# j310_lna.net
KiCad netlist of a schematic drawn in EAGLE
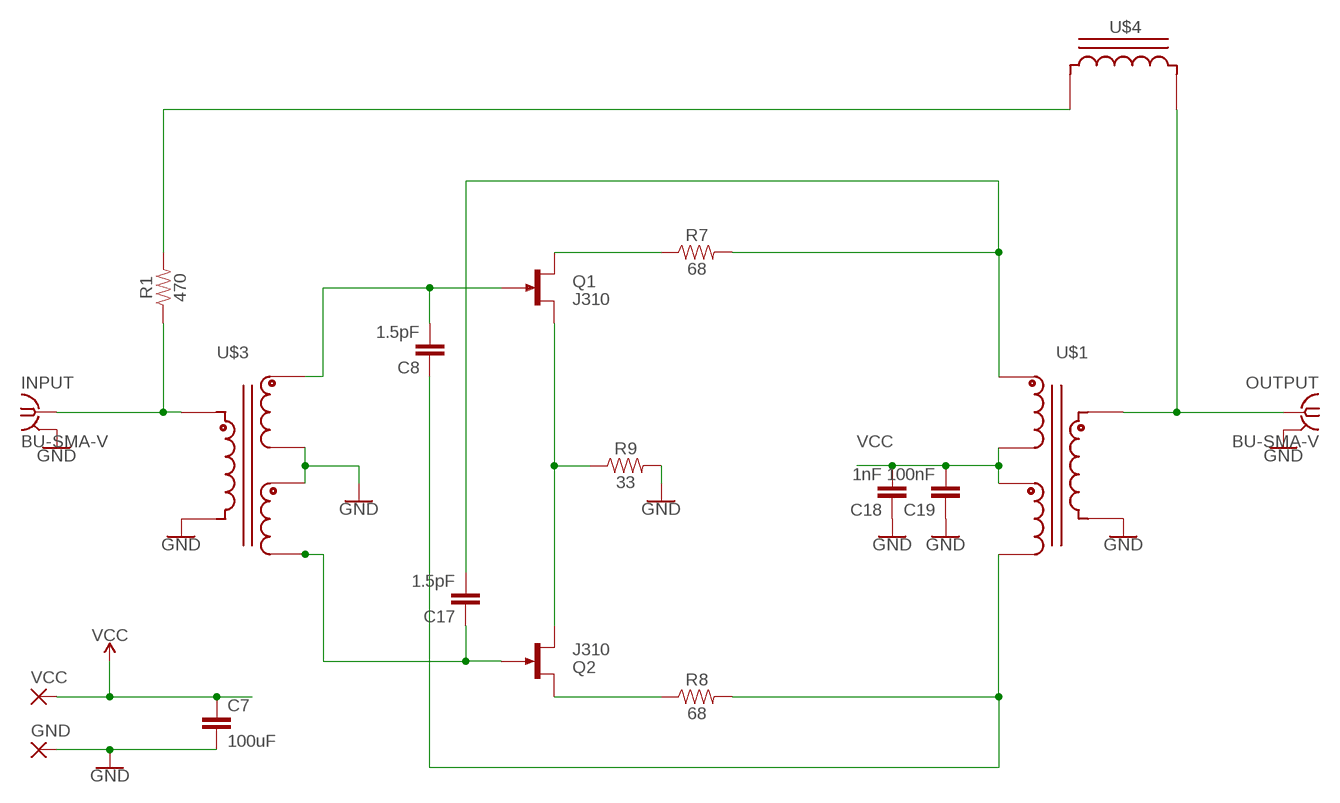
[diagram p0: schematic, sheet 1]

(export (version "E")
  (design (tool "Eeschema 10.0.6"))
  (components
    (comp (ref "C7")
      (value "100uF")
      (footprint "eagle-import:C5B3.5")
      (libsource (lib "eagle-import") (part "C5/3.5"))
    )
    (comp (ref "C8")
      (value "1.5pF")
      (footprint "eagle-import:C5B3.5")
      (libsource (lib "eagle-import") (part "C5/3.5"))
    )
    (comp (ref "C17")
      (value "1.5pF")
      (footprint "eagle-import:C5B3.5")
      (libsource (lib "eagle-import") (part "C5/3.5"))
    )
    (comp (ref "C18")
      (value "1nF")
      (footprint "eagle-import:C5B3.5")
      (libsource (lib "eagle-import") (part "C5/3.5"))
    )
    (comp (ref "C19")
      (value "100nF")
      (footprint "eagle-import:C5B3.5")
      (libsource (lib "eagle-import") (part "C5/3.5"))
    )
    (comp (ref "GND")
      (value "3,17/1,1")
      (footprint "eagle-import:3,17_1,1")
      (libsource (lib "eagle-import") (part "3,17/1,1"))
    )
    (comp (ref "INPUT")
      (value "BU-SMA-V")
      (footprint "eagle-import:BU-SMA-V")
      (libsource (lib "eagle-import") (part "BU-SMA-V"))
    )
    (comp (ref "OUTPUT")
      (value "BU-SMA-V")
      (footprint "eagle-import:BU-SMA-V")
      (libsource (lib "eagle-import") (part "BU-SMA-V"))
    )
    (comp (ref "Q1")
      (value "J310")
      (footprint "eagle-import:TO92R")
      (libsource (lib "eagle-import") (part "J310"))
    )
    (comp (ref "Q2")
      (value "J310")
      (footprint "eagle-import:TO92R")
      (libsource (lib "eagle-import") (part "J310"))
    )
    (comp (ref "R1")
      (value "470")
      (footprint "eagle-import:AXIAL-0.3")
      (libsource (lib "eagle-import") (part "1KOHM-HORIZ-1/4W-1%"))
    )
    (comp (ref "R7")
      (value "68")
      (footprint "eagle-import:AXIAL-0.3")
      (libsource (lib "eagle-import") (part "1KOHM-HORIZ-1/4W-1%"))
    )
    (comp (ref "R8")
      (value "68")
      (footprint "eagle-import:AXIAL-0.3")
      (libsource (lib "eagle-import") (part "1KOHM-HORIZ-1/4W-1%"))
    )
    (comp (ref "R9")
      (value "33")
      (footprint "eagle-import:AXIAL-0.3")
      (libsource (lib "eagle-import") (part "1KOHM-HORIZ-1/4W-1%"))
    )
    (comp (ref "U$1")
      (value "T50_SPLITTER")
      (footprint "eagle-import:T50_SPLITTER")
      (libsource (lib "eagle-import") (part "T50_SPLITTER"))
    )
    (comp (ref "U$3")
      (value "T50_SPLITTER")
      (footprint "eagle-import:T50_SPLITTER")
      (libsource (lib "eagle-import") (part "T50_SPLITTER"))
    )
    (comp (ref "U$4")
      (value "T37_INDUCTOR")
      (footprint "eagle-import:T37_INDUCTOR")
      (libsource (lib "eagle-import") (part "T37_INDUCTOR"))
    )
    (comp (ref "VCC")
      (value "3,17/1,1")
      (footprint "eagle-import:3,17_1,1")
      (libsource (lib "eagle-import") (part "3,17/1,1"))
    )
  )
  (nets
    (net (code "1") (name "GND") (class "Default")
      (node (ref "C18") (pin "1") (pinfunction "1_1") (pintype "passive"))
      (node (ref "C19") (pin "1") (pinfunction "1_1") (pintype "passive"))
      (node (ref "C7") (pin "2") (pinfunction "2_2") (pintype "passive"))
      (node (ref "GND") (pin "1") (pinfunction "P_1") (pintype "passive"))
      (node (ref "INPUT") (pin "2") (pinfunction "2_2") (pintype "passive"))
      (node (ref "INPUT") (pin "3") (pinfunction "2_3") (pintype "passive"))
      (node (ref "INPUT") (pin "4") (pinfunction "2_4") (pintype "passive"))
      (node (ref "INPUT") (pin "5") (pinfunction "2_5") (pintype "passive"))
      (node (ref "OUTPUT") (pin "2") (pinfunction "2_2") (pintype "passive"))
      (node (ref "OUTPUT") (pin "3") (pinfunction "2_3") (pintype "passive"))
      (node (ref "OUTPUT") (pin "4") (pinfunction "2_4") (pintype "passive"))
      (node (ref "OUTPUT") (pin "5") (pinfunction "2_5") (pintype "passive"))
      (node (ref "R9") (pin "P$2") (pinfunction "2_P$2") (pintype "passive"))
      (node (ref "U$1") (pin "C1A") (pinfunction "C1A_C1A") (pintype "bidirectional"))
      (node (ref "U$3") (pin "C1A") (pinfunction "C1A_C1A") (pintype "bidirectional"))
      (node (ref "U$3") (pin "C2A") (pinfunction "C3B_C2A") (pintype "bidirectional"))
      (node (ref "U$3") (pin "C3A") (pinfunction "C2A_C3A") (pintype "bidirectional"))
    )
    (net (code "2") (name "Net-(OUTPUT-Pad1)") (class "Default")
      (node (ref "OUTPUT") (pin "1") (pinfunction "1_1") (pintype "passive"))
      (node (ref "U$1") (pin "C1B") (pinfunction "C1B_C1B") (pintype "bidirectional"))
      (node (ref "U$4") (pin "CA") (pinfunction "CA_CA") (pintype "bidirectional"))
    )
    (net (code "3") (name "Net-(R1-1)") (class "Default")
      (node (ref "INPUT") (pin "1") (pinfunction "1_1") (pintype "passive"))
      (node (ref "R1") (pin "P$1") (pinfunction "1_P$1") (pintype "passive"))
      (node (ref "U$3") (pin "C1B") (pinfunction "C1B_C1B") (pintype "bidirectional"))
    )
    (net (code "4") (name "Net-(R1-2)") (class "Default")
      (node (ref "R1") (pin "P$2") (pinfunction "2_P$2") (pintype "passive"))
      (node (ref "U$4") (pin "CB") (pinfunction "CB_CB") (pintype "bidirectional"))
    )
    (net (code "5") (name "Net-(R7-1)") (class "Default")
      (node (ref "Q1") (pin "D") (pinfunction "D_D") (pintype "passive"))
      (node (ref "R7") (pin "P$1") (pinfunction "1_P$1") (pintype "passive"))
    )
    (net (code "6") (name "Net-(R7-2)") (class "Default")
      (node (ref "C17") (pin "2") (pinfunction "2_2") (pintype "passive"))
      (node (ref "R7") (pin "P$2") (pinfunction "2_P$2") (pintype "passive"))
      (node (ref "U$1") (pin "C3B") (pinfunction "C2B_C3B") (pintype "bidirectional"))
    )
    (net (code "7") (name "Net-(R8-1)") (class "Default")
      (node (ref "Q2") (pin "D") (pinfunction "D_D") (pintype "passive"))
      (node (ref "R8") (pin "P$1") (pinfunction "1_P$1") (pintype "passive"))
    )
    (net (code "8") (name "Net-(R8-2)") (class "Default")
      (node (ref "C8") (pin "1") (pinfunction "1_1") (pintype "passive"))
      (node (ref "R8") (pin "P$2") (pinfunction "2_P$2") (pintype "passive"))
      (node (ref "U$1") (pin "C2B") (pinfunction "C3A_C2B") (pintype "bidirectional"))
    )
    (net (code "9") (name "Net-(R9-1)") (class "Default")
      (node (ref "Q1") (pin "S") (pinfunction "S_S") (pintype "passive"))
      (node (ref "Q2") (pin "S") (pinfunction "S_S") (pintype "passive"))
      (node (ref "R9") (pin "P$1") (pinfunction "1_P$1") (pintype "passive"))
    )
    (net (code "10") (name "Net-(U$3-C2B)") (class "Default")
      (node (ref "C8") (pin "2") (pinfunction "2_2") (pintype "passive"))
      (node (ref "Q1") (pin "G") (pinfunction "G_G") (pintype "passive"))
      (node (ref "U$3") (pin "C3B") (pinfunction "C2B_C3B") (pintype "bidirectional"))
    )
    (net (code "11") (name "Net-(U$3-C3A)") (class "Default")
      (node (ref "C17") (pin "1") (pinfunction "1_1") (pintype "passive"))
      (node (ref "Q2") (pin "G") (pinfunction "G_G") (pintype "passive"))
      (node (ref "U$3") (pin "C2B") (pinfunction "C3A_C2B") (pintype "bidirectional"))
    )
    (net (code "12") (name "VCC") (class "Default")
      (node (ref "C18") (pin "2") (pinfunction "2_2") (pintype "passive"))
      (node (ref "C19") (pin "2") (pinfunction "2_2") (pintype "passive"))
      (node (ref "C7") (pin "1") (pinfunction "1_1") (pintype "passive"))
      (node (ref "U$1") (pin "C2A") (pinfunction "C3B_C2A") (pintype "bidirectional"))
      (node (ref "U$1") (pin "C3A") (pinfunction "C2A_C3A") (pintype "bidirectional"))
      (node (ref "VCC") (pin "1") (pinfunction "P_1") (pintype "passive"))
    )
  )
)
